# anbisonique.net
KiCad netlist of a schematic drawn in EAGLE
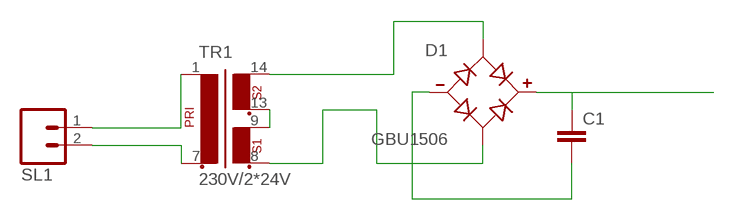
[diagram p0: schematic, sheet 1]

(export (version "E")
  (design (tool "Eeschema 10.0.6"))
  (components
    (comp (ref "C1")
      (value "C-EUC0603")
      (footprint "eagle-import:C0603")
      (libsource (lib "eagle-import") (part "C-EUC0603"))
    )
    (comp (ref "D1")
      (value "GBU1506")
      (footprint "eagle-import:SIP343W114P508L2205H2134Q4")
      (fields (field (name "MF") "Taiwan Semiconductor Corporation"))
      (libsource (lib "eagle-import") (part "GBU1506"))
    )
    (comp (ref "SL1")
      (value "M02")
      (footprint "eagle-import:02P")
      (libsource (lib "eagle-import") (part "M02"))
    )
    (comp (ref "TR1")
      (value "230V/2*24V")
      (footprint "eagle-import:EI60-2")
      (libsource (lib "eagle-import") (part "EI60-2"))
    )
  )
  (nets
    (net (code "1") (name "Net-(C1-Pad1)") (class "Default")
      (node (ref "C1") (pin "1") (pinfunction "1_1") (pintype "passive"))
      (node (ref "D1") (pin "+") (pinfunction "+_+") (pintype "passive"))
    )
    (net (code "2") (name "Net-(C1-Pad2)") (class "Default")
      (node (ref "C1") (pin "2") (pinfunction "2_2") (pintype "passive"))
      (node (ref "D1") (pin "-") (pinfunction "-_-") (pintype "passive"))
    )
    (net (code "3") (name "Net-(SL1-Pad1)") (class "Default")
      (node (ref "SL1") (pin "1") (pinfunction "1_1") (pintype "passive"))
      (node (ref "TR1") (pin "1") (pinfunction "1_1") (pintype "passive"))
    )
    (net (code "4") (name "Net-(TR1-2)") (class "Default")
      (node (ref "SL1") (pin "2") (pinfunction "2_2") (pintype "passive"))
      (node (ref "TR1") (pin "7") (pinfunction "2_7") (pintype "passive"))
    )
    (net (code "5") (name "Net-(TR1-3)") (class "Default")
      (node (ref "D1") (pin "AC2") (pinfunction "AC2_AC2") (pintype "passive"))
      (node (ref "TR1") (pin "8") (pinfunction "3_8") (pintype "passive"))
    )
    (net (code "6") (name "Net-(TR1-4)") (class "Default")
      (node (ref "TR1") (pin "13") (pinfunction "5_13") (pintype "passive"))
      (node (ref "TR1") (pin "9") (pinfunction "4_9") (pintype "passive"))
    )
    (net (code "7") (name "Net-(TR1-6)") (class "Default")
      (node (ref "D1") (pin "AC1") (pinfunction "AC1_AC1") (pintype "passive"))
      (node (ref "TR1") (pin "14") (pinfunction "6_14") (pintype "passive"))
    )
  )
)
